# 08_FPGA_banks_5_6_7_8.net
KiCad netlist of a schematic drawn in Altium Designer
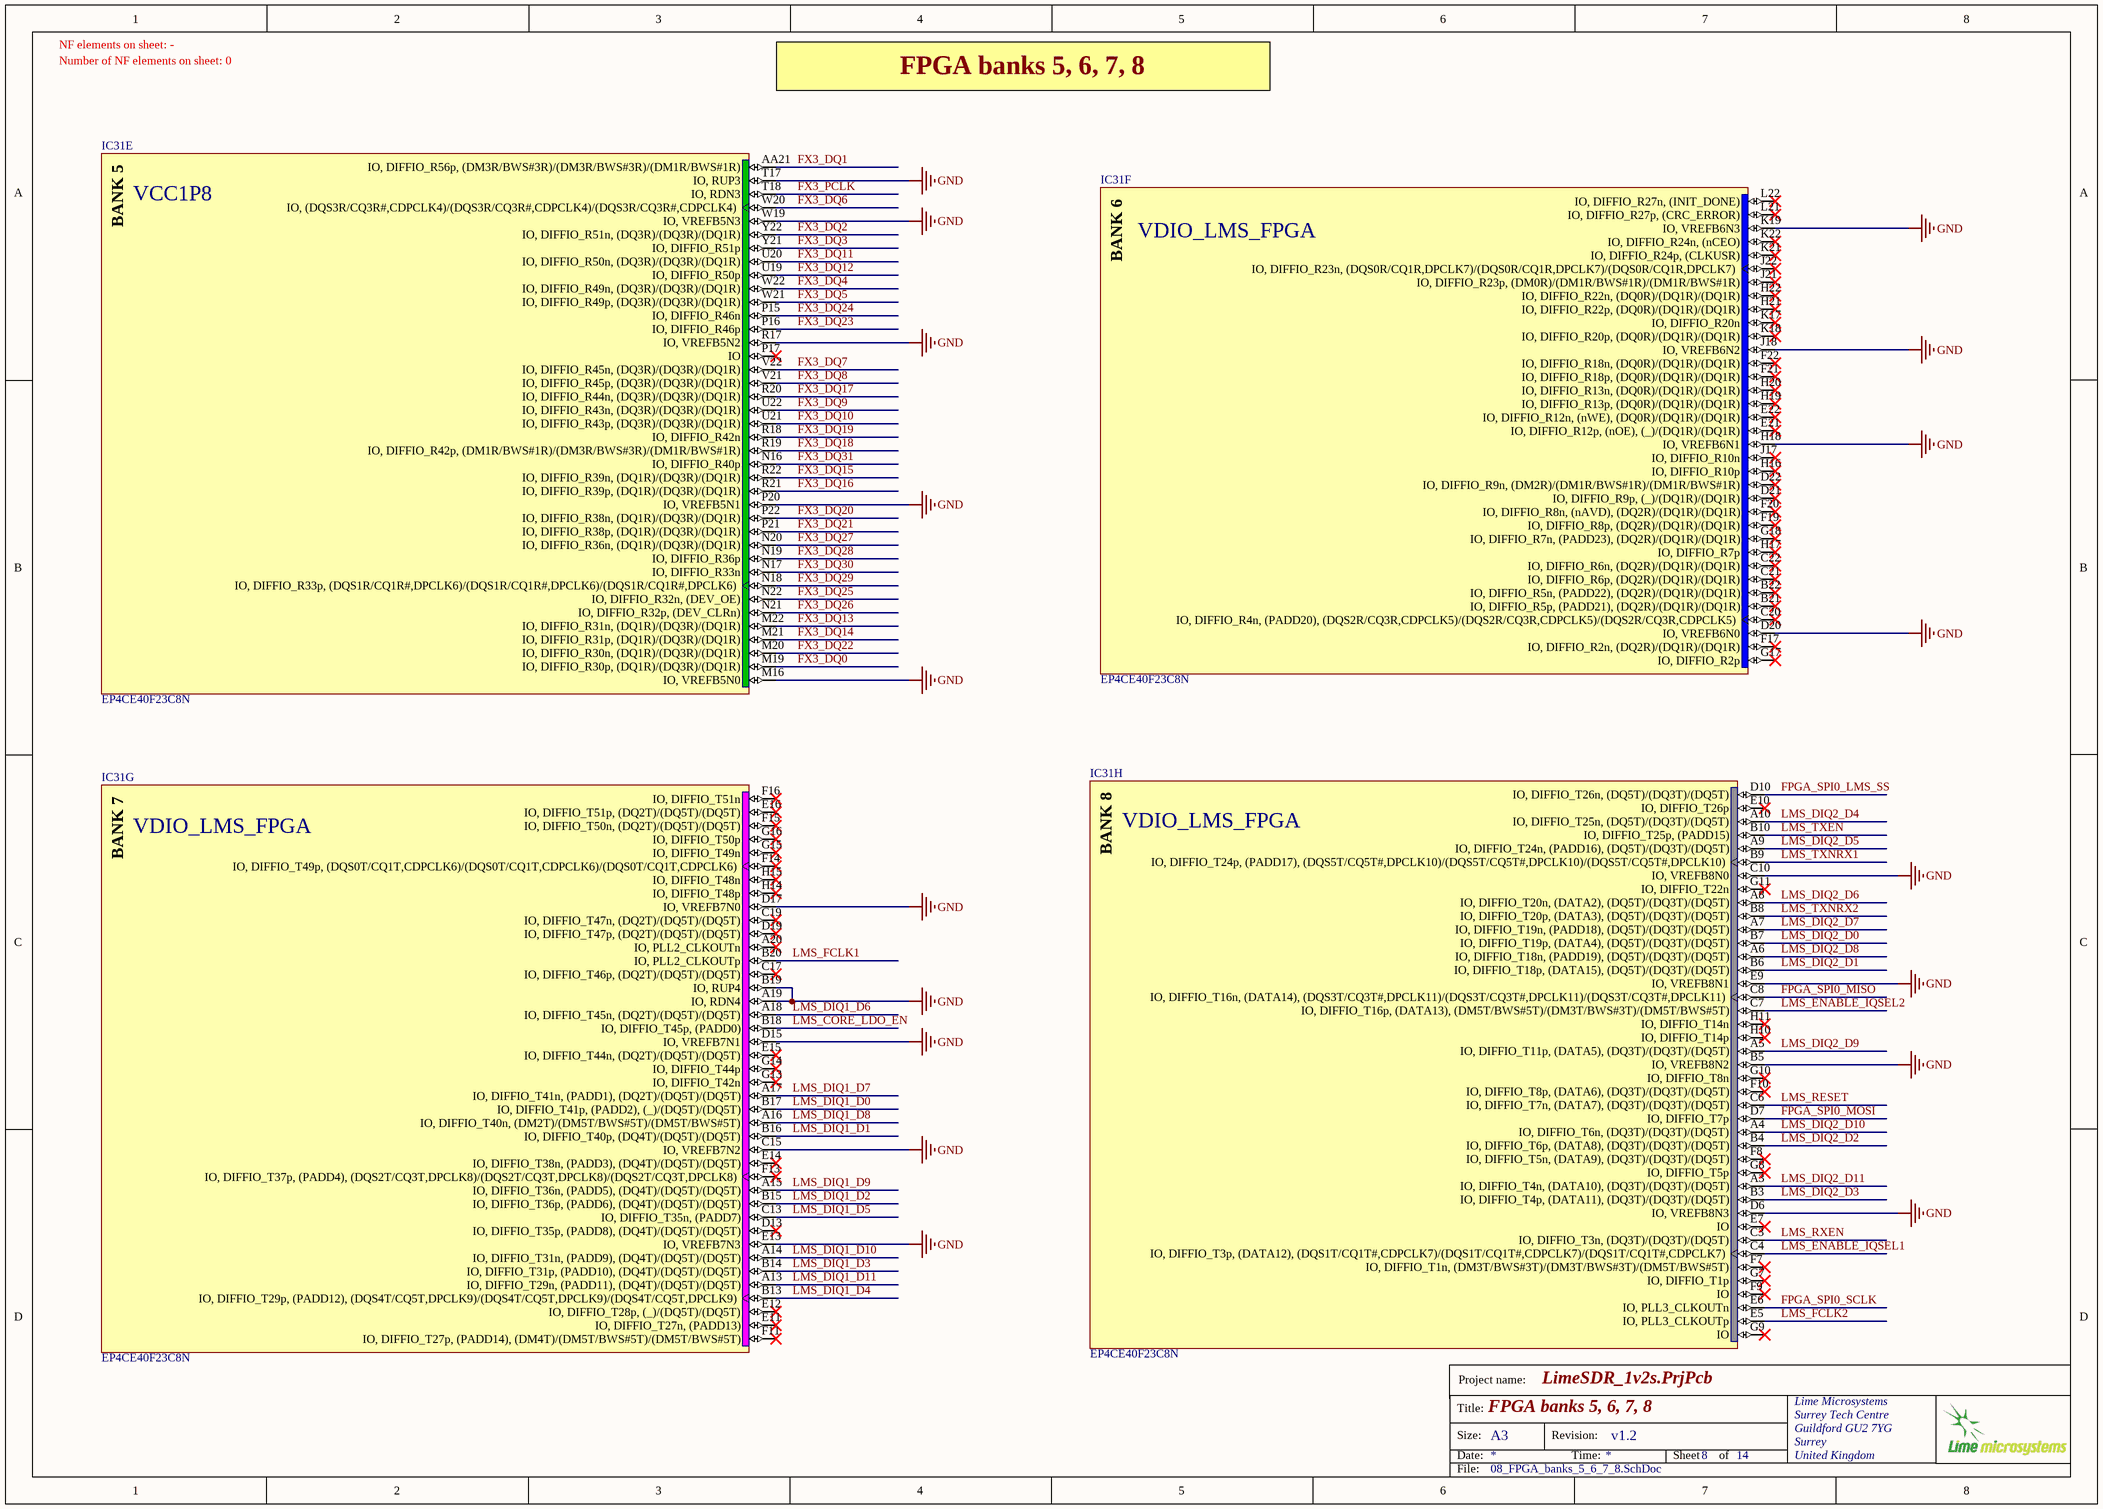
[diagram p0: 08_FPGA_banks_5_6_7_8.SchDoc]

(export (version "E")
  (design (tool "Eeschema 10.0.6"))
  (components
    (comp (ref "IC31")
      (value "EP4CE40F23C8N")
      (footprint "FBGA484_A-240")
      (description "IC FPGA 328 I/O 484FBGA")
      (fields (field (name "MANUFACTURER") "Altera"))
      (libsource (lib "LimeMicroAltiumLib_schLib") (part "EP4CE40F23C7N"))
    )
  )
  (nets
    (net (code "1") (name "/FPGA_SPI0_LMS_SS") (class "Default")
      (node (ref "IC31") (pin "D10") (pinfunction "IO,_DIFFIO_T26n,_(DQ5T)/(DQ3T)/(DQ5T)_D10") (pintype "bidirectional"))
    )
    (net (code "2") (name "/FPGA_SPI0_MISO") (class "Default")
      (node (ref "IC31") (pin "C8") (pinfunction "IO,_DIFFIO_T16n,_(DATA14),_(DQS3T/CQ3T#,DPCLK11)/(DQS3T/CQ3T#,DPCLK11)/(DQS3T/CQ3T#,DPCLK11)_C8") (pintype "bidirectional"))
    )
    (net (code "3") (name "/FPGA_SPI0_MOSI") (class "Default")
      (node (ref "IC31") (pin "D7") (pinfunction "IO,_DIFFIO_T7p_D7") (pintype "bidirectional"))
    )
    (net (code "4") (name "/FPGA_SPI0_SCLK") (class "Default")
      (node (ref "IC31") (pin "E6") (pinfunction "IO,_PLL3_CLKOUTn_E6") (pintype "bidirectional"))
    )
    (net (code "5") (name "/FX3_DQ0") (class "Default")
      (node (ref "IC31") (pin "M19") (pinfunction "IO,_DIFFIO_R30p,_(DQ1R)/(DQ3R)/(DQ1R)_M19") (pintype "bidirectional"))
    )
    (net (code "6") (name "/FX3_DQ1") (class "Default")
      (node (ref "IC31") (pin "AA21") (pinfunction "IO,_DIFFIO_R56p,_(DM3R/BWS#3R)/(DM3R/BWS#3R)/(DM1R/BWS#1R)_AA21") (pintype "bidirectional"))
    )
    (net (code "7") (name "/FX3_DQ2") (class "Default")
      (node (ref "IC31") (pin "Y22") (pinfunction "IO,_DIFFIO_R51n,_(DQ3R)/(DQ3R)/(DQ1R)_Y22") (pintype "bidirectional"))
    )
    (net (code "8") (name "/FX3_DQ3") (class "Default")
      (node (ref "IC31") (pin "Y21") (pinfunction "IO,_DIFFIO_R51p_Y21") (pintype "bidirectional"))
    )
    (net (code "9") (name "/FX3_DQ4") (class "Default")
      (node (ref "IC31") (pin "W22") (pinfunction "IO,_DIFFIO_R49n,_(DQ3R)/(DQ3R)/(DQ1R)_W22") (pintype "bidirectional"))
    )
    (net (code "10") (name "/FX3_DQ5") (class "Default")
      (node (ref "IC31") (pin "W21") (pinfunction "IO,_DIFFIO_R49p,_(DQ3R)/(DQ3R)/(DQ1R)_W21") (pintype "bidirectional"))
    )
    (net (code "11") (name "/FX3_DQ6") (class "Default")
      (node (ref "IC31") (pin "W20") (pinfunction "IO,_(DQS3R/CQ3R#,CDPCLK4)/(DQS3R/CQ3R#,CDPCLK4)/(DQS3R/CQ3R#,CDPCLK4)_W20") (pintype "bidirectional"))
    )
    (net (code "12") (name "/FX3_DQ7") (class "Default")
      (node (ref "IC31") (pin "V22") (pinfunction "IO,_DIFFIO_R45n,_(DQ3R)/(DQ3R)/(DQ1R)_V22") (pintype "bidirectional"))
    )
    (net (code "13") (name "/FX3_DQ8") (class "Default")
      (node (ref "IC31") (pin "V21") (pinfunction "IO,_DIFFIO_R45p,_(DQ3R)/(DQ3R)/(DQ1R)_V21") (pintype "bidirectional"))
    )
    (net (code "14") (name "/FX3_DQ9") (class "Default")
      (node (ref "IC31") (pin "U22") (pinfunction "IO,_DIFFIO_R43n,_(DQ3R)/(DQ3R)/(DQ1R)_U22") (pintype "bidirectional"))
    )
    (net (code "15") (name "/FX3_DQ10") (class "Default")
      (node (ref "IC31") (pin "U21") (pinfunction "IO,_DIFFIO_R43p,_(DQ3R)/(DQ3R)/(DQ1R)_U21") (pintype "bidirectional"))
    )
    (net (code "16") (name "/FX3_DQ11") (class "Default")
      (node (ref "IC31") (pin "U20") (pinfunction "IO,_DIFFIO_R50n,_(DQ3R)/(DQ3R)/(DQ1R)_U20") (pintype "bidirectional"))
    )
    (net (code "17") (name "/FX3_DQ12") (class "Default")
      (node (ref "IC31") (pin "U19") (pinfunction "IO,_DIFFIO_R50p_U19") (pintype "bidirectional"))
    )
    (net (code "18") (name "/FX3_DQ13") (class "Default")
      (node (ref "IC31") (pin "M22") (pinfunction "IO,_DIFFIO_R31n,_(DQ1R)/(DQ3R)/(DQ1R)_M22") (pintype "bidirectional"))
    )
    (net (code "19") (name "/FX3_DQ14") (class "Default")
      (node (ref "IC31") (pin "M21") (pinfunction "IO,_DIFFIO_R31p,_(DQ1R)/(DQ3R)/(DQ1R)_M21") (pintype "bidirectional"))
    )
    (net (code "20") (name "/FX3_DQ15") (class "Default")
      (node (ref "IC31") (pin "R22") (pinfunction "IO,_DIFFIO_R39n,_(DQ1R)/(DQ3R)/(DQ1R)_R22") (pintype "bidirectional"))
    )
    (net (code "21") (name "/FX3_DQ16") (class "Default")
      (node (ref "IC31") (pin "R21") (pinfunction "IO,_DIFFIO_R39p,_(DQ1R)/(DQ3R)/(DQ1R)_R21") (pintype "bidirectional"))
    )
    (net (code "22") (name "/FX3_DQ17") (class "Default")
      (node (ref "IC31") (pin "R20") (pinfunction "IO,_DIFFIO_R44n,_(DQ3R)/(DQ3R)/(DQ1R)_R20") (pintype "bidirectional"))
    )
    (net (code "23") (name "/FX3_DQ18") (class "Default")
      (node (ref "IC31") (pin "R19") (pinfunction "IO,_DIFFIO_R42p,_(DM1R/BWS#1R)/(DM3R/BWS#3R)/(DM1R/BWS#1R)_R19") (pintype "bidirectional"))
    )
    (net (code "24") (name "/FX3_DQ19") (class "Default")
      (node (ref "IC31") (pin "R18") (pinfunction "IO,_DIFFIO_R42n_R18") (pintype "bidirectional"))
    )
    (net (code "25") (name "/FX3_DQ20") (class "Default")
      (node (ref "IC31") (pin "P22") (pinfunction "IO,_DIFFIO_R38n,_(DQ1R)/(DQ3R)/(DQ1R)_P22") (pintype "bidirectional"))
    )
    (net (code "26") (name "/FX3_DQ21") (class "Default")
      (node (ref "IC31") (pin "P21") (pinfunction "IO,_DIFFIO_R38p,_(DQ1R)/(DQ3R)/(DQ1R)_P21") (pintype "bidirectional"))
    )
    (net (code "27") (name "/FX3_DQ22") (class "Default")
      (node (ref "IC31") (pin "M20") (pinfunction "IO,_DIFFIO_R30n,_(DQ1R)/(DQ3R)/(DQ1R)_M20") (pintype "bidirectional"))
    )
    (net (code "28") (name "/FX3_DQ23") (class "Default")
      (node (ref "IC31") (pin "P16") (pinfunction "IO,_DIFFIO_R46p_P16") (pintype "bidirectional"))
    )
    (net (code "29") (name "/FX3_DQ24") (class "Default")
      (node (ref "IC31") (pin "P15") (pinfunction "IO,_DIFFIO_R46n_P15") (pintype "bidirectional"))
    )
    (net (code "30") (name "/FX3_DQ25") (class "Default")
      (node (ref "IC31") (pin "N22") (pinfunction "IO,_DIFFIO_R32n,_(DEV_OE)_N22") (pintype "bidirectional"))
    )
    (net (code "31") (name "/FX3_DQ26") (class "Default")
      (node (ref "IC31") (pin "N21") (pinfunction "IO,_DIFFIO_R32p,_(DEV_CLRn)_N21") (pintype "bidirectional"))
    )
    (net (code "32") (name "/FX3_DQ27") (class "Default")
      (node (ref "IC31") (pin "N20") (pinfunction "IO,_DIFFIO_R36n,_(DQ1R)/(DQ3R)/(DQ1R)_N20") (pintype "bidirectional"))
    )
    (net (code "33") (name "/FX3_DQ28") (class "Default")
      (node (ref "IC31") (pin "N19") (pinfunction "IO,_DIFFIO_R36p_N19") (pintype "bidirectional"))
    )
    (net (code "34") (name "/FX3_DQ29") (class "Default")
      (node (ref "IC31") (pin "N18") (pinfunction "IO,_DIFFIO_R33p,_(DQS1R/CQ1R#,DPCLK6)/(DQS1R/CQ1R#,DPCLK6)/(DQS1R/CQ1R#,DPCLK6)_N18") (pintype "bidirectional"))
    )
    (net (code "35") (name "/FX3_DQ30") (class "Default")
      (node (ref "IC31") (pin "N17") (pinfunction "IO,_DIFFIO_R33n_N17") (pintype "bidirectional"))
    )
    (net (code "36") (name "/FX3_DQ31") (class "Default")
      (node (ref "IC31") (pin "N16") (pinfunction "IO,_DIFFIO_R40p_N16") (pintype "bidirectional"))
    )
    (net (code "37") (name "/FX3_PCLK") (class "Default")
      (node (ref "IC31") (pin "T18") (pinfunction "IO,_RDN3_T18") (pintype "bidirectional"))
    )
    (net (code "38") (name "/LMS_CORE_LDO_EN") (class "Default")
      (node (ref "IC31") (pin "B18") (pinfunction "IO,_DIFFIO_T45p,_(PADD0)_B18") (pintype "bidirectional"))
    )
    (net (code "39") (name "/LMS_DIQ1_D0") (class "Default")
      (node (ref "IC31") (pin "B17") (pinfunction "IO,_DIFFIO_T41p,_(PADD2),_(_)/(DQ5T)/(DQ5T)_B17") (pintype "bidirectional"))
    )
    (net (code "40") (name "/LMS_DIQ1_D1") (class "Default")
      (node (ref "IC31") (pin "B16") (pinfunction "IO,_DIFFIO_T40p,_(DQ4T)/(DQ5T)/(DQ5T)_B16") (pintype "bidirectional"))
    )
    (net (code "41") (name "/LMS_DIQ1_D2") (class "Default")
      (node (ref "IC31") (pin "B15") (pinfunction "IO,_DIFFIO_T36p,_(PADD6),_(DQ4T)/(DQ5T)/(DQ5T)_B15") (pintype "bidirectional"))
    )
    (net (code "42") (name "/LMS_DIQ1_D3") (class "Default")
      (node (ref "IC31") (pin "B14") (pinfunction "IO,_DIFFIO_T31p,_(PADD10),_(DQ4T)/(DQ5T)/(DQ5T)_B14") (pintype "bidirectional"))
    )
    (net (code "43") (name "/LMS_DIQ1_D4") (class "Default")
      (node (ref "IC31") (pin "B13") (pinfunction "IO,_DIFFIO_T29p,_(PADD12),_(DQS4T/CQ5T,DPCLK9)/(DQS4T/CQ5T,DPCLK9)/(DQS4T/CQ5T,DPCLK9)_B13") (pintype "bidirectional"))
    )
    (net (code "44") (name "/LMS_DIQ1_D5") (class "Default")
      (node (ref "IC31") (pin "C13") (pinfunction "IO,_DIFFIO_T35n,_(PADD7)_C13") (pintype "bidirectional"))
    )
    (net (code "45") (name "/LMS_DIQ1_D6") (class "Default")
      (node (ref "IC31") (pin "A18") (pinfunction "IO,_DIFFIO_T45n,_(DQ2T)/(DQ5T)/(DQ5T)_A18") (pintype "bidirectional"))
    )
    (net (code "46") (name "/LMS_DIQ1_D7") (class "Default")
      (node (ref "IC31") (pin "A17") (pinfunction "IO,_DIFFIO_T41n,_(PADD1),_(DQ2T)/(DQ5T)/(DQ5T)_A17") (pintype "bidirectional"))
    )
    (net (code "47") (name "/LMS_DIQ1_D8") (class "Default")
      (node (ref "IC31") (pin "A16") (pinfunction "IO,_DIFFIO_T40n,_(DM2T)/(DM5T/BWS#5T)/(DM5T/BWS#5T)_A16") (pintype "bidirectional"))
    )
    (net (code "48") (name "/LMS_DIQ1_D9") (class "Default")
      (node (ref "IC31") (pin "A15") (pinfunction "IO,_DIFFIO_T36n,_(PADD5),_(DQ4T)/(DQ5T)/(DQ5T)_A15") (pintype "bidirectional"))
    )
    (net (code "49") (name "/LMS_DIQ1_D10") (class "Default")
      (node (ref "IC31") (pin "A14") (pinfunction "IO,_DIFFIO_T31n,_(PADD9),_(DQ4T)/(DQ5T)/(DQ5T)_A14") (pintype "bidirectional"))
    )
    (net (code "50") (name "/LMS_DIQ1_D11") (class "Default")
      (node (ref "IC31") (pin "A13") (pinfunction "IO,_DIFFIO_T29n,_(PADD11),_(DQ4T)/(DQ5T)/(DQ5T)_A13") (pintype "bidirectional"))
    )
    (net (code "51") (name "/LMS_DIQ2_D0") (class "Default")
      (node (ref "IC31") (pin "B7") (pinfunction "IO,_DIFFIO_T19p,_(DATA4),_(DQ5T)/(DQ3T)/(DQ5T)_B7") (pintype "bidirectional"))
    )
    (net (code "52") (name "/LMS_DIQ2_D1") (class "Default")
      (node (ref "IC31") (pin "B6") (pinfunction "IO,_DIFFIO_T18p,_(DATA15),_(DQ5T)/(DQ3T)/(DQ5T)_B6") (pintype "bidirectional"))
    )
    (net (code "53") (name "/LMS_DIQ2_D2") (class "Default")
      (node (ref "IC31") (pin "B4") (pinfunction "IO,_DIFFIO_T6p,_(DATA8),_(DQ3T)/(DQ3T)/(DQ5T)_B4") (pintype "bidirectional"))
    )
    (net (code "54") (name "/LMS_DIQ2_D3") (class "Default")
      (node (ref "IC31") (pin "B3") (pinfunction "IO,_DIFFIO_T4p,_(DATA11),_(DQ3T)/(DQ3T)/(DQ5T)_B3") (pintype "bidirectional"))
    )
    (net (code "55") (name "/LMS_DIQ2_D4") (class "Default")
      (node (ref "IC31") (pin "A10") (pinfunction "IO,_DIFFIO_T25n,_(DQ5T)/(DQ3T)/(DQ5T)_A10") (pintype "bidirectional"))
    )
    (net (code "56") (name "/LMS_DIQ2_D5") (class "Default")
      (node (ref "IC31") (pin "A9") (pinfunction "IO,_DIFFIO_T24n,_(PADD16),_(DQ5T)/(DQ3T)/(DQ5T)_A9") (pintype "bidirectional"))
    )
    (net (code "57") (name "/LMS_DIQ2_D6") (class "Default")
      (node (ref "IC31") (pin "A8") (pinfunction "IO,_DIFFIO_T20n,_(DATA2),_(DQ5T)/(DQ3T)/(DQ5T)_A8") (pintype "bidirectional"))
    )
    (net (code "58") (name "/LMS_DIQ2_D7") (class "Default")
      (node (ref "IC31") (pin "A7") (pinfunction "IO,_DIFFIO_T19n,_(PADD18),_(DQ5T)/(DQ3T)/(DQ5T)_A7") (pintype "bidirectional"))
    )
    (net (code "59") (name "/LMS_DIQ2_D8") (class "Default")
      (node (ref "IC31") (pin "A6") (pinfunction "IO,_DIFFIO_T18n,_(PADD19),_(DQ5T)/(DQ3T)/(DQ5T)_A6") (pintype "bidirectional"))
    )
    (net (code "60") (name "/LMS_DIQ2_D9") (class "Default")
      (node (ref "IC31") (pin "A5") (pinfunction "IO,_DIFFIO_T11p,_(DATA5),_(DQ3T)/(DQ3T)/(DQ5T)_A5") (pintype "bidirectional"))
    )
    (net (code "61") (name "/LMS_DIQ2_D10") (class "Default")
      (node (ref "IC31") (pin "A4") (pinfunction "IO,_DIFFIO_T6n,_(DQ3T)/(DQ3T)/(DQ5T)_A4") (pintype "bidirectional"))
    )
    (net (code "62") (name "/LMS_DIQ2_D11") (class "Default")
      (node (ref "IC31") (pin "A3") (pinfunction "IO,_DIFFIO_T4n,_(DATA10),_(DQ3T)/(DQ3T)/(DQ5T)_A3") (pintype "bidirectional"))
    )
    (net (code "63") (name "/LMS_ENABLE_IQSEL1") (class "Default")
      (node (ref "IC31") (pin "C4") (pinfunction "IO,_DIFFIO_T3p,_(DATA12),_(DQS1T/CQ1T#,CDPCLK7)/(DQS1T/CQ1T#,CDPCLK7)/(DQS1T/CQ1T#,CDPCLK7)_C4") (pintype "bidirectional"))
    )
    (net (code "64") (name "/LMS_ENABLE_IQSEL2") (class "Default")
      (node (ref "IC31") (pin "C7") (pinfunction "IO,_DIFFIO_T16p,_(DATA13),_(DM5T/BWS#5T)/(DM3T/BWS#3T)/(DM5T/BWS#5T)_C7") (pintype "bidirectional"))
    )
    (net (code "65") (name "/LMS_FCLK1") (class "Default")
      (node (ref "IC31") (pin "B20") (pinfunction "IO,_PLL2_CLKOUTp_B20") (pintype "bidirectional"))
    )
    (net (code "66") (name "/LMS_FCLK2") (class "Default")
      (node (ref "IC31") (pin "E5") (pinfunction "IO,_PLL3_CLKOUTp_E5") (pintype "bidirectional"))
    )
    (net (code "67") (name "/LMS_RESET") (class "Default")
      (node (ref "IC31") (pin "C6") (pinfunction "IO,_DIFFIO_T7n,_(DATA7),_(DQ3T)/(DQ3T)/(DQ5T)_C6") (pintype "bidirectional"))
    )
    (net (code "68") (name "/LMS_RXEN") (class "Default")
      (node (ref "IC31") (pin "C3") (pinfunction "IO,_DIFFIO_T3n,_(DQ3T)/(DQ3T)/(DQ5T)_C3") (pintype "bidirectional"))
    )
    (net (code "69") (name "/LMS_TXEN") (class "Default")
      (node (ref "IC31") (pin "B10") (pinfunction "IO,_DIFFIO_T25p,_(PADD15)_B10") (pintype "bidirectional"))
    )
    (net (code "70") (name "/LMS_TXNRX1") (class "Default")
      (node (ref "IC31") (pin "B9") (pinfunction "IO,_DIFFIO_T24p,_(PADD17),_(DQS5T/CQ5T#,DPCLK10)/(DQS5T/CQ5T#,DPCLK10)/(DQS5T/CQ5T#,DPCLK10)_B9") (pintype "bidirectional"))
    )
    (net (code "71") (name "/LMS_TXNRX2") (class "Default")
      (node (ref "IC31") (pin "B8") (pinfunction "IO,_DIFFIO_T20p,_(DATA3),_(DQ5T)/(DQ3T)/(DQ5T)_B8") (pintype "bidirectional"))
    )
    (net (code "72") (name "GND") (class "Default")
      (node (ref "IC31") (pin "A19") (pinfunction "IO,_RDN4_A19") (pintype "bidirectional"))
      (node (ref "IC31") (pin "B19") (pinfunction "IO,_RUP4_B19") (pintype "bidirectional"))
      (node (ref "IC31") (pin "B5") (pinfunction "IO,_VREFB8N2_B5") (pintype "bidirectional"))
      (node (ref "IC31") (pin "C10") (pinfunction "IO,_VREFB8N0_C10") (pintype "bidirectional"))
      (node (ref "IC31") (pin "C15") (pinfunction "IO,_VREFB7N2_C15") (pintype "bidirectional"))
      (node (ref "IC31") (pin "D15") (pinfunction "IO,_VREFB7N1_D15") (pintype "bidirectional"))
      (node (ref "IC31") (pin "D17") (pinfunction "IO,_VREFB7N0_D17") (pintype "bidirectional"))
      (node (ref "IC31") (pin "D20") (pinfunction "IO,_VREFB6N0_D20") (pintype "bidirectional"))
      (node (ref "IC31") (pin "D6") (pinfunction "IO,_VREFB8N3_D6") (pintype "bidirectional"))
      (node (ref "IC31") (pin "E13") (pinfunction "IO,_VREFB7N3_E13") (pintype "bidirectional"))
      (node (ref "IC31") (pin "E9") (pinfunction "IO,_VREFB8N1_E9") (pintype "bidirectional"))
      (node (ref "IC31") (pin "H18") (pinfunction "IO,_VREFB6N1_H18") (pintype "bidirectional"))
      (node (ref "IC31") (pin "J18") (pinfunction "IO,_VREFB6N2_J18") (pintype "bidirectional"))
      (node (ref "IC31") (pin "K19") (pinfunction "IO,_VREFB6N3_K19") (pintype "bidirectional"))
      (node (ref "IC31") (pin "M16") (pinfunction "IO,_VREFB5N0_M16") (pintype "bidirectional"))
      (node (ref "IC31") (pin "P20") (pinfunction "IO,_VREFB5N1_P20") (pintype "bidirectional"))
      (node (ref "IC31") (pin "R17") (pinfunction "IO,_VREFB5N2_R17") (pintype "bidirectional"))
      (node (ref "IC31") (pin "T17") (pinfunction "IO,_RUP3_T17") (pintype "bidirectional"))
      (node (ref "IC31") (pin "W19") (pinfunction "IO,_VREFB5N3_W19") (pintype "bidirectional"))
    )
    (net (code "73") (name "unconnected-(IC31E-IO-PadP17)") (class "Default")
      (node (ref "IC31") (pin "P17") (pinfunction "IO_P17") (pintype "bidirectional+no_connect"))
    )
    (net (code "74") (name "unconnected-(IC31F-IO,_DIFFIO_R2n,_(DQ2R){slash}(DQ1R){slash}(DQ1R)-PadF17)") (class "Default")
      (node (ref "IC31") (pin "F17") (pinfunction "IO,_DIFFIO_R2n,_(DQ2R)/(DQ1R)/(DQ1R)_F17") (pintype "bidirectional+no_connect"))
    )
    (net (code "75") (name "unconnected-(IC31F-IO,_DIFFIO_R2p-PadG17)") (class "Default")
      (node (ref "IC31") (pin "G17") (pinfunction "IO,_DIFFIO_R2p_G17") (pintype "bidirectional+no_connect"))
    )
    (net (code "76") (name "unconnected-(IC31F-IO,_DIFFIO_R4n,_(PADD20),_(DQS2R{slash}CQ3R,CDPCLK5){slash}(DQS2R{slash}CQ3R,CDPCLK5){slash}(DQS2R{slash}CQ3R,CDPCLK5)-PadC20)") (class "Default")
      (node (ref "IC31") (pin "C20") (pinfunction "IO,_DIFFIO_R4n,_(PADD20),_(DQS2R/CQ3R,CDPCLK5)/(DQS2R/CQ3R,CDPCLK5)/(DQS2R/CQ3R,CDPCLK5)_C20") (pintype "bidirectional+no_connect"))
    )
    (net (code "77") (name "unconnected-(IC31F-IO,_DIFFIO_R5n,_(PADD22),_(DQ2R){slash}(DQ1R){slash}(DQ1R)-PadB22)") (class "Default")
      (node (ref "IC31") (pin "B22") (pinfunction "IO,_DIFFIO_R5n,_(PADD22),_(DQ2R)/(DQ1R)/(DQ1R)_B22") (pintype "bidirectional+no_connect"))
    )
    (net (code "78") (name "unconnected-(IC31F-IO,_DIFFIO_R5p,_(PADD21),_(DQ2R){slash}(DQ1R){slash}(DQ1R)-PadB21)") (class "Default")
      (node (ref "IC31") (pin "B21") (pinfunction "IO,_DIFFIO_R5p,_(PADD21),_(DQ2R)/(DQ1R)/(DQ1R)_B21") (pintype "bidirectional+no_connect"))
    )
    (net (code "79") (name "unconnected-(IC31F-IO,_DIFFIO_R6n,_(DQ2R){slash}(DQ1R){slash}(DQ1R)-PadC22)") (class "Default")
      (node (ref "IC31") (pin "C22") (pinfunction "IO,_DIFFIO_R6n,_(DQ2R)/(DQ1R)/(DQ1R)_C22") (pintype "bidirectional+no_connect"))
    )
    (net (code "80") (name "unconnected-(IC31F-IO,_DIFFIO_R6p,_(DQ2R){slash}(DQ1R){slash}(DQ1R)-PadC21)") (class "Default")
      (node (ref "IC31") (pin "C21") (pinfunction "IO,_DIFFIO_R6p,_(DQ2R)/(DQ1R)/(DQ1R)_C21") (pintype "bidirectional+no_connect"))
    )
    (net (code "81") (name "unconnected-(IC31F-IO,_DIFFIO_R7n,_(PADD23),_(DQ2R){slash}(DQ1R){slash}(DQ1R)-PadG18)") (class "Default")
      (node (ref "IC31") (pin "G18") (pinfunction "IO,_DIFFIO_R7n,_(PADD23),_(DQ2R)/(DQ1R)/(DQ1R)_G18") (pintype "bidirectional+no_connect"))
    )
    (net (code "82") (name "unconnected-(IC31F-IO,_DIFFIO_R7p-PadH17)") (class "Default")
      (node (ref "IC31") (pin "H17") (pinfunction "IO,_DIFFIO_R7p_H17") (pintype "bidirectional+no_connect"))
    )
    (net (code "83") (name "unconnected-(IC31F-IO,_DIFFIO_R8n,_(nAVD),_(DQ2R){slash}(DQ1R){slash}(DQ1R)-PadF20)") (class "Default")
      (node (ref "IC31") (pin "F20") (pinfunction "IO,_DIFFIO_R8n,_(nAVD),_(DQ2R)/(DQ1R)/(DQ1R)_F20") (pintype "bidirectional+no_connect"))
    )
    (net (code "84") (name "unconnected-(IC31F-IO,_DIFFIO_R8p,_(DQ2R){slash}(DQ1R){slash}(DQ1R)-PadF19)") (class "Default")
      (node (ref "IC31") (pin "F19") (pinfunction "IO,_DIFFIO_R8p,_(DQ2R)/(DQ1R)/(DQ1R)_F19") (pintype "bidirectional+no_connect"))
    )
    (net (code "85") (name "unconnected-(IC31F-IO,_DIFFIO_R9n,_(DM2R){slash}(DM1R{slash}BWS#1R){slash}(DM1R{slash}BWS#1R)-PadD22)") (class "Default")
      (node (ref "IC31") (pin "D22") (pinfunction "IO,_DIFFIO_R9n,_(DM2R)/(DM1R/BWS#1R)/(DM1R/BWS#1R)_D22") (pintype "bidirectional+no_connect"))
    )
    (net (code "86") (name "unconnected-(IC31F-IO,_DIFFIO_R9p,_(_){slash}(DQ1R){slash}(DQ1R)-PadD21)") (class "Default")
      (node (ref "IC31") (pin "D21") (pinfunction "IO,_DIFFIO_R9p,_(_)/(DQ1R)/(DQ1R)_D21") (pintype "bidirectional+no_connect"))
    )
    (net (code "87") (name "unconnected-(IC31F-IO,_DIFFIO_R10n-PadJ17)") (class "Default")
      (node (ref "IC31") (pin "J17") (pinfunction "IO,_DIFFIO_R10n_J17") (pintype "bidirectional+no_connect"))
    )
    (net (code "88") (name "unconnected-(IC31F-IO,_DIFFIO_R10p-PadH16)") (class "Default")
      (node (ref "IC31") (pin "H16") (pinfunction "IO,_DIFFIO_R10p_H16") (pintype "bidirectional+no_connect"))
    )
    (net (code "89") (name "unconnected-(IC31F-IO,_DIFFIO_R12n,_(nWE),_(DQ0R){slash}(DQ1R){slash}(DQ1R)-PadE22)") (class "Default")
      (node (ref "IC31") (pin "E22") (pinfunction "IO,_DIFFIO_R12n,_(nWE),_(DQ0R)/(DQ1R)/(DQ1R)_E22") (pintype "bidirectional+no_connect"))
    )
    (net (code "90") (name "unconnected-(IC31F-IO,_DIFFIO_R12p,_(nOE),_(_){slash}(DQ1R){slash}(DQ1R)-PadE21)") (class "Default")
      (node (ref "IC31") (pin "E21") (pinfunction "IO,_DIFFIO_R12p,_(nOE),_(_)/(DQ1R)/(DQ1R)_E21") (pintype "bidirectional+no_connect"))
    )
    (net (code "91") (name "unconnected-(IC31F-IO,_DIFFIO_R13n,_(DQ0R){slash}(DQ1R){slash}(DQ1R)-PadH20)") (class "Default")
      (node (ref "IC31") (pin "H20") (pinfunction "IO,_DIFFIO_R13n,_(DQ0R)/(DQ1R)/(DQ1R)_H20") (pintype "bidirectional+no_connect"))
    )
    (net (code "92") (name "unconnected-(IC31F-IO,_DIFFIO_R13p,_(DQ0R){slash}(DQ1R){slash}(DQ1R)-PadH19)") (class "Default")
      (node (ref "IC31") (pin "H19") (pinfunction "IO,_DIFFIO_R13p,_(DQ0R)/(DQ1R)/(DQ1R)_H19") (pintype "bidirectional+no_connect"))
    )
    (net (code "93") (name "unconnected-(IC31F-IO,_DIFFIO_R18n,_(DQ0R){slash}(DQ1R){slash}(DQ1R)-PadF22)") (class "Default")
      (node (ref "IC31") (pin "F22") (pinfunction "IO,_DIFFIO_R18n,_(DQ0R)/(DQ1R)/(DQ1R)_F22") (pintype "bidirectional+no_connect"))
    )
    (net (code "94") (name "unconnected-(IC31F-IO,_DIFFIO_R18p,_(DQ0R){slash}(DQ1R){slash}(DQ1R)-PadF21)") (class "Default")
      (node (ref "IC31") (pin "F21") (pinfunction "IO,_DIFFIO_R18p,_(DQ0R)/(DQ1R)/(DQ1R)_F21") (pintype "bidirectional+no_connect"))
    )
    (net (code "95") (name "unconnected-(IC31F-IO,_DIFFIO_R20n-PadK17)") (class "Default")
      (node (ref "IC31") (pin "K17") (pinfunction "IO,_DIFFIO_R20n_K17") (pintype "bidirectional+no_connect"))
    )
    (net (code "96") (name "unconnected-(IC31F-IO,_DIFFIO_R20p,_(DQ0R){slash}(DQ1R){slash}(DQ1R)-PadK18)") (class "Default")
      (node (ref "IC31") (pin "K18") (pinfunction "IO,_DIFFIO_R20p,_(DQ0R)/(DQ1R)/(DQ1R)_K18") (pintype "bidirectional+no_connect"))
    )
    (net (code "97") (name "unconnected-(IC31F-IO,_DIFFIO_R22n,_(DQ0R){slash}(DQ1R){slash}(DQ1R)-PadH22)") (class "Default")
      (node (ref "IC31") (pin "H22") (pinfunction "IO,_DIFFIO_R22n,_(DQ0R)/(DQ1R)/(DQ1R)_H22") (pintype "bidirectional+no_connect"))
    )
    (net (code "98") (name "unconnected-(IC31F-IO,_DIFFIO_R22p,_(DQ0R){slash}(DQ1R){slash}(DQ1R)-PadH21)") (class "Default")
      (node (ref "IC31") (pin "H21") (pinfunction "IO,_DIFFIO_R22p,_(DQ0R)/(DQ1R)/(DQ1R)_H21") (pintype "bidirectional+no_connect"))
    )
    (net (code "99") (name "unconnected-(IC31F-IO,_DIFFIO_R23n,_(DQS0R{slash}CQ1R,DPCLK7){slash}(DQS0R{slash}CQ1R,DPCLK7){slash}(DQS0R{slash}CQ1R,DPCLK7)-PadJ22)") (class "Default")
      (node (ref "IC31") (pin "J22") (pinfunction "IO,_DIFFIO_R23n,_(DQS0R/CQ1R,DPCLK7)/(DQS0R/CQ1R,DPCLK7)/(DQS0R/CQ1R,DPCLK7)_J22") (pintype "bidirectional+no_connect"))
    )
    (net (code "100") (name "unconnected-(IC31F-IO,_DIFFIO_R23p,_(DM0R){slash}(DM1R{slash}BWS#1R){slash}(DM1R{slash}BWS#1R)-PadJ21)") (class "Default")
      (node (ref "IC31") (pin "J21") (pinfunction "IO,_DIFFIO_R23p,_(DM0R)/(DM1R/BWS#1R)/(DM1R/BWS#1R)_J21") (pintype "bidirectional+no_connect"))
    )
    (net (code "101") (name "unconnected-(IC31F-IO,_DIFFIO_R24n,_(nCEO)-PadK22)") (class "Default")
      (node (ref "IC31") (pin "K22") (pinfunction "IO,_DIFFIO_R24n,_(nCEO)_K22") (pintype "bidirectional+no_connect"))
    )
    (net (code "102") (name "unconnected-(IC31F-IO,_DIFFIO_R24p,_(CLKUSR)-PadK21)") (class "Default")
      (node (ref "IC31") (pin "K21") (pinfunction "IO,_DIFFIO_R24p,_(CLKUSR)_K21") (pintype "bidirectional+no_connect"))
    )
    (net (code "103") (name "unconnected-(IC31F-IO,_DIFFIO_R27n,_(INIT_DONE)-PadL22)") (class "Default")
      (node (ref "IC31") (pin "L22") (pinfunction "IO,_DIFFIO_R27n,_(INIT_DONE)_L22") (pintype "bidirectional+no_connect"))
    )
    (net (code "104") (name "unconnected-(IC31F-IO,_DIFFIO_R27p,_(CRC_ERROR)-PadL21)") (class "Default")
      (node (ref "IC31") (pin "L21") (pinfunction "IO,_DIFFIO_R27p,_(CRC_ERROR)_L21") (pintype "bidirectional+no_connect"))
    )
    (net (code "105") (name "unconnected-(IC31G-IO,_DIFFIO_T27n,_(PADD13)-PadE11)") (class "Default")
      (node (ref "IC31") (pin "E11") (pinfunction "IO,_DIFFIO_T27n,_(PADD13)_E11") (pintype "bidirectional+no_connect"))
    )
    (net (code "106") (name "unconnected-(IC31G-IO,_DIFFIO_T27p,_(PADD14),_(DM4T){slash}(DM5T{slash}BWS#5T){slash}(DM5T{slash}BWS#5T)-PadF11)") (class "Default")
      (node (ref "IC31") (pin "F11") (pinfunction "IO,_DIFFIO_T27p,_(PADD14),_(DM4T)/(DM5T/BWS#5T)/(DM5T/BWS#5T)_F11") (pintype "bidirectional+no_connect"))
    )
    (net (code "107") (name "unconnected-(IC31G-IO,_DIFFIO_T28p,_(_){slash}(DQ5T){slash}(DQ5T)-PadE12)") (class "Default")
      (node (ref "IC31") (pin "E12") (pinfunction "IO,_DIFFIO_T28p,_(_)/(DQ5T)/(DQ5T)_E12") (pintype "bidirectional+no_connect"))
    )
    (net (code "108") (name "unconnected-(IC31G-IO,_DIFFIO_T35p,_(PADD8),_(DQ4T){slash}(DQ5T){slash}(DQ5T)-PadD13)") (class "Default")
      (node (ref "IC31") (pin "D13") (pinfunction "IO,_DIFFIO_T35p,_(PADD8),_(DQ4T)/(DQ5T)/(DQ5T)_D13") (pintype "bidirectional+no_connect"))
    )
    (net (code "109") (name "unconnected-(IC31G-IO,_DIFFIO_T37p,_(PADD4),_(DQS2T{slash}CQ3T,DPCLK8){slash}(DQS2T{slash}CQ3T,DPCLK8){slash}(DQS2T{slash}CQ3T,DPCLK8)-PadF13)") (class "Default")
      (node (ref "IC31") (pin "F13") (pinfunction "IO,_DIFFIO_T37p,_(PADD4),_(DQS2T/CQ3T,DPCLK8)/(DQS2T/CQ3T,DPCLK8)/(DQS2T/CQ3T,DPCLK8)_F13") (pintype "bidirectional+no_connect"))
    )
    (net (code "110") (name "unconnected-(IC31G-IO,_DIFFIO_T38n,_(PADD3),_(DQ4T){slash}(DQ5T){slash}(DQ5T)-PadE14)") (class "Default")
      (node (ref "IC31") (pin "E14") (pinfunction "IO,_DIFFIO_T38n,_(PADD3),_(DQ4T)/(DQ5T)/(DQ5T)_E14") (pintype "bidirectional+no_connect"))
    )
    (net (code "111") (name "unconnected-(IC31G-IO,_DIFFIO_T42n-PadG13)") (class "Default")
      (node (ref "IC31") (pin "G13") (pinfunction "IO,_DIFFIO_T42n_G13") (pintype "bidirectional+no_connect"))
    )
    (net (code "112") (name "unconnected-(IC31G-IO,_DIFFIO_T44n,_(DQ2T){slash}(DQ5T){slash}(DQ5T)-PadE15)") (class "Default")
      (node (ref "IC31") (pin "E15") (pinfunction "IO,_DIFFIO_T44n,_(DQ2T)/(DQ5T)/(DQ5T)_E15") (pintype "bidirectional+no_connect"))
    )
    (net (code "113") (name "unconnected-(IC31G-IO,_DIFFIO_T44p-PadG14)") (class "Default")
      (node (ref "IC31") (pin "G14") (pinfunction "IO,_DIFFIO_T44p_G14") (pintype "bidirectional+no_connect"))
    )
    (net (code "114") (name "unconnected-(IC31G-IO,_DIFFIO_T46p,_(DQ2T){slash}(DQ5T){slash}(DQ5T)-PadC17)") (class "Default")
      (node (ref "IC31") (pin "C17") (pinfunction "IO,_DIFFIO_T46p,_(DQ2T)/(DQ5T)/(DQ5T)_C17") (pintype "bidirectional+no_connect"))
    )
    (net (code "115") (name "unconnected-(IC31G-IO,_DIFFIO_T47n,_(DQ2T){slash}(DQ5T){slash}(DQ5T)-PadC19)") (class "Default")
      (node (ref "IC31") (pin "C19") (pinfunction "IO,_DIFFIO_T47n,_(DQ2T)/(DQ5T)/(DQ5T)_C19") (pintype "bidirectional+no_connect"))
    )
    (net (code "116") (name "unconnected-(IC31G-IO,_DIFFIO_T47p,_(DQ2T){slash}(DQ5T){slash}(DQ5T)-PadD19)") (class "Default")
      (node (ref "IC31") (pin "D19") (pinfunction "IO,_DIFFIO_T47p,_(DQ2T)/(DQ5T)/(DQ5T)_D19") (pintype "bidirectional+no_connect"))
    )
    (net (code "117") (name "unconnected-(IC31G-IO,_DIFFIO_T48n-PadH15)") (class "Default")
      (node (ref "IC31") (pin "H15") (pinfunction "IO,_DIFFIO_T48n_H15") (pintype "bidirectional+no_connect"))
    )
    (net (code "118") (name "unconnected-(IC31G-IO,_DIFFIO_T48p-PadH14)") (class "Default")
      (node (ref "IC31") (pin "H14") (pinfunction "IO,_DIFFIO_T48p_H14") (pintype "bidirectional+no_connect"))
    )
    (net (code "119") (name "unconnected-(IC31G-IO,_DIFFIO_T49n-PadG15)") (class "Default")
      (node (ref "IC31") (pin "G15") (pinfunction "IO,_DIFFIO_T49n_G15") (pintype "bidirectional+no_connect"))
    )
    (net (code "120") (name "unconnected-(IC31G-IO,_DIFFIO_T49p,_(DQS0T{slash}CQ1T,CDPCLK6){slash}(DQS0T{slash}CQ1T,CDPCLK6){slash}(DQS0T{slash}CQ1T,CDPCLK6)-PadF14)") (class "Default")
      (node (ref "IC31") (pin "F14") (pinfunction "IO,_DIFFIO_T49p,_(DQS0T/CQ1T,CDPCLK6)/(DQS0T/CQ1T,CDPCLK6)/(DQS0T/CQ1T,CDPCLK6)_F14") (pintype "bidirectional+no_connect"))
    )
    (net (code "121") (name "unconnected-(IC31G-IO,_DIFFIO_T50n,_(DQ2T){slash}(DQ5T){slash}(DQ5T)-PadF15)") (class "Default")
      (node (ref "IC31") (pin "F15") (pinfunction "IO,_DIFFIO_T50n,_(DQ2T)/(DQ5T)/(DQ5T)_F15") (pintype "bidirectional+no_connect"))
    )
    (net (code "122") (name "unconnected-(IC31G-IO,_DIFFIO_T50p-PadG16)") (class "Default")
      (node (ref "IC31") (pin "G16") (pinfunction "IO,_DIFFIO_T50p_G16") (pintype "bidirectional+no_connect"))
    )
    (net (code "123") (name "unconnected-(IC31G-IO,_DIFFIO_T51n-PadF16)") (class "Default")
      (node (ref "IC31") (pin "F16") (pinfunction "IO,_DIFFIO_T51n_F16") (pintype "bidirectional+no_connect"))
    )
    (net (code "124") (name "unconnected-(IC31G-IO,_DIFFIO_T51p,_(DQ2T){slash}(DQ5T){slash}(DQ5T)-PadE16)") (class "Default")
      (node (ref "IC31") (pin "E16") (pinfunction "IO,_DIFFIO_T51p,_(DQ2T)/(DQ5T)/(DQ5T)_E16") (pintype "bidirectional+no_connect"))
    )
    (net (code "125") (name "unconnected-(IC31G-IO,_PLL2_CLKOUTn-PadA20)") (class "Default")
      (node (ref "IC31") (pin "A20") (pinfunction "IO,_PLL2_CLKOUTn_A20") (pintype "bidirectional+no_connect"))
    )
    (net (code "126") (name "unconnected-(IC31H-IO,_DIFFIO_T1n,_(DM3T{slash}BWS#3T){slash}(DM3T{slash}BWS#3T){slash}(DM5T{slash}BWS#5T)-PadF7)") (class "Default")
      (node (ref "IC31") (pin "F7") (pinfunction "IO,_DIFFIO_T1n,_(DM3T/BWS#3T)/(DM3T/BWS#3T)/(DM5T/BWS#5T)_F7") (pintype "bidirectional+no_connect"))
    )
    (net (code "127") (name "unconnected-(IC31H-IO,_DIFFIO_T1p-PadG7)") (class "Default")
      (node (ref "IC31") (pin "G7") (pinfunction "IO,_DIFFIO_T1p_G7") (pintype "bidirectional+no_connect"))
    )
    (net (code "128") (name "unconnected-(IC31H-IO,_DIFFIO_T5n,_(DATA9),_(DQ3T){slash}(DQ3T){slash}(DQ5T)-PadF8)") (class "Default")
      (node (ref "IC31") (pin "F8") (pinfunction "IO,_DIFFIO_T5n,_(DATA9),_(DQ3T)/(DQ3T)/(DQ5T)_F8") (pintype "bidirectional+no_connect"))
    )
    (net (code "129") (name "unconnected-(IC31H-IO,_DIFFIO_T5p-PadG8)") (class "Default")
      (node (ref "IC31") (pin "G8") (pinfunction "IO,_DIFFIO_T5p_G8") (pintype "bidirectional+no_connect"))
    )
    (net (code "130") (name "unconnected-(IC31H-IO,_DIFFIO_T8n-PadG10)") (class "Default")
      (node (ref "IC31") (pin "G10") (pinfunction "IO,_DIFFIO_T8n_G10") (pintype "bidirectional+no_connect"))
    )
    (net (code "131") (name "unconnected-(IC31H-IO,_DIFFIO_T8p,_(DATA6),_(DQ3T){slash}(DQ3T){slash}(DQ5T)-PadF10)") (class "Default")
      (node (ref "IC31") (pin "F10") (pinfunction "IO,_DIFFIO_T8p,_(DATA6),_(DQ3T)/(DQ3T)/(DQ5T)_F10") (pintype "bidirectional+no_connect"))
    )
    (net (code "132") (name "unconnected-(IC31H-IO,_DIFFIO_T14n-PadH11)") (class "Default")
      (node (ref "IC31") (pin "H11") (pinfunction "IO,_DIFFIO_T14n_H11") (pintype "bidirectional+no_connect"))
    )
    (net (code "133") (name "unconnected-(IC31H-IO,_DIFFIO_T14p-PadH10)") (class "Default")
      (node (ref "IC31") (pin "H10") (pinfunction "IO,_DIFFIO_T14p_H10") (pintype "bidirectional+no_connect"))
    )
    (net (code "134") (name "unconnected-(IC31H-IO,_DIFFIO_T22n-PadG11)") (class "Default")
      (node (ref "IC31") (pin "G11") (pinfunction "IO,_DIFFIO_T22n_G11") (pintype "bidirectional+no_connect"))
    )
    (net (code "135") (name "unconnected-(IC31H-IO,_DIFFIO_T26p-PadE10)") (class "Default")
      (node (ref "IC31") (pin "E10") (pinfunction "IO,_DIFFIO_T26p_E10") (pintype "bidirectional+no_connect"))
    )
    (net (code "136") (name "unconnected-(IC31H-IO-PadE7)") (class "Default")
      (node (ref "IC31") (pin "E7") (pinfunction "IO_E7") (pintype "bidirectional+no_connect"))
    )
    (net (code "137") (name "unconnected-(IC31H-IO-PadF9)") (class "Default")
      (node (ref "IC31") (pin "F9") (pinfunction "IO_F9") (pintype "bidirectional+no_connect"))
    )
    (net (code "138") (name "unconnected-(IC31H-IO-PadG9)") (class "Default")
      (node (ref "IC31") (pin "G9") (pinfunction "IO_G9") (pintype "bidirectional+no_connect"))
    )
  )
)
